# AC-DC5V.net
KiCad netlist of a schematic drawn in EAGLE
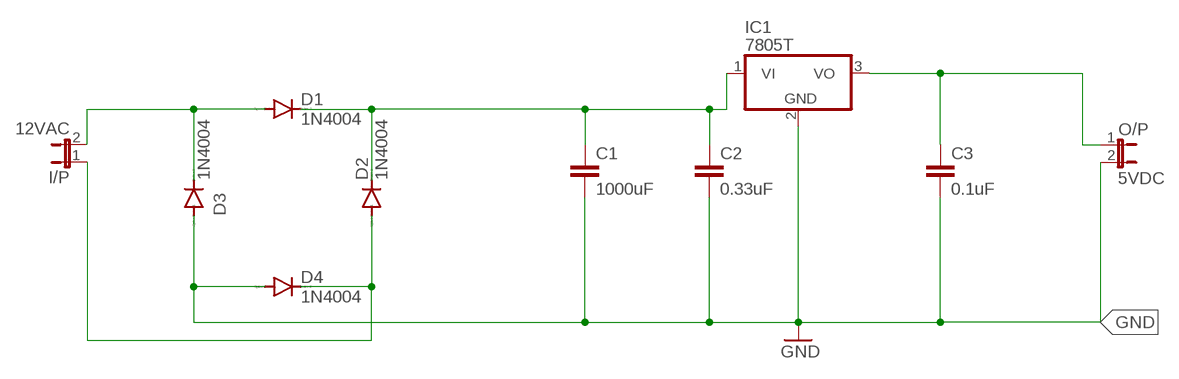
[diagram p0: schematic, sheet 1]

(export (version "E")
  (design (tool "Eeschema 10.0.6"))
  (components
    (comp (ref "C1")
      (value "1000uF")
      (footprint "eagle-import:C2.5-3")
      (libsource (lib "eagle-import") (part "C2,5-3"))
    )
    (comp (ref "C2")
      (value "0.33uF")
      (footprint "eagle-import:C2.5-3")
      (libsource (lib "eagle-import") (part "C2,5-3"))
    )
    (comp (ref "C3")
      (value "0.1uF")
      (footprint "eagle-import:C2.5-3")
      (libsource (lib "eagle-import") (part "C2,5-3"))
    )
    (comp (ref "D1")
      (value "1N4004")
      (footprint "eagle-import:DO41-10")
      (libsource (lib "eagle-import") (part "1N4004"))
    )
    (comp (ref "D2")
      (value "1N4004")
      (footprint "eagle-import:DO41-10")
      (libsource (lib "eagle-import") (part "1N4004"))
    )
    (comp (ref "D3")
      (value "1N4004")
      (footprint "eagle-import:DO41-10")
      (libsource (lib "eagle-import") (part "1N4004"))
    )
    (comp (ref "D4")
      (value "1N4004")
      (footprint "eagle-import:DO41-10")
      (libsource (lib "eagle-import") (part "1N4004"))
    )
    (comp (ref "I/P")
      (value "12VAC")
      (footprint "eagle-import:JP1")
      (libsource (lib "eagle-import") (part "JP1E"))
    )
    (comp (ref "IC1")
      (value "7805T")
      (footprint "eagle-import:TO220H")
      (libsource (lib "eagle-import") (part "78T05"))
    )
    (comp (ref "O/P")
      (value "5VDC")
      (footprint "eagle-import:JP1")
      (libsource (lib "eagle-import") (part "JP1E"))
    )
  )
  (nets
    (net (code "1") (name "GND") (class "Default")
      (node (ref "C1") (pin "2") (pinfunction "2_2") (pintype "passive"))
      (node (ref "C2") (pin "2") (pinfunction "2_2") (pintype "passive"))
      (node (ref "C3") (pin "2") (pinfunction "2_2") (pintype "passive"))
      (node (ref "D3") (pin "A") (pinfunction "A_A") (pintype "passive"))
      (node (ref "D4") (pin "A") (pinfunction "A_A") (pintype "passive"))
      (node (ref "IC1") (pin "2") (pinfunction "GND_2") (pintype "passive"))
      (node (ref "O/P") (pin "2") (pinfunction "2_2") (pintype "passive"))
    )
    (net (code "2") (name "Net-(D1-PadA)") (class "Default")
      (node (ref "D1") (pin "A") (pinfunction "A_A") (pintype "passive"))
      (node (ref "D3") (pin "C") (pinfunction "C_C") (pintype "passive"))
      (node (ref "I/P") (pin "2") (pinfunction "2_2") (pintype "passive"))
    )
    (net (code "3") (name "Net-(D2-PadA)") (class "Default")
      (node (ref "D2") (pin "A") (pinfunction "A_A") (pintype "passive"))
      (node (ref "D4") (pin "C") (pinfunction "C_C") (pintype "passive"))
      (node (ref "I/P") (pin "1") (pinfunction "1_1") (pintype "passive"))
    )
    (net (code "4") (name "Net-(IC1-VI)") (class "Default")
      (node (ref "C1") (pin "1") (pinfunction "1_1") (pintype "passive"))
      (node (ref "C2") (pin "1") (pinfunction "1_1") (pintype "passive"))
      (node (ref "D1") (pin "C") (pinfunction "C_C") (pintype "passive"))
      (node (ref "D2") (pin "C") (pinfunction "C_C") (pintype "passive"))
      (node (ref "IC1") (pin "1") (pinfunction "VI_1") (pintype "input"))
    )
    (net (code "5") (name "Net-(IC1-VO)") (class "Default")
      (node (ref "C3") (pin "1") (pinfunction "1_1") (pintype "passive"))
      (node (ref "IC1") (pin "3") (pinfunction "VO_3") (pintype "passive"))
      (node (ref "O/P") (pin "1") (pinfunction "1_1") (pintype "passive"))
    )
  )
)
